# Sheet1.net
KiCad netlist of a schematic drawn in Altium Designer
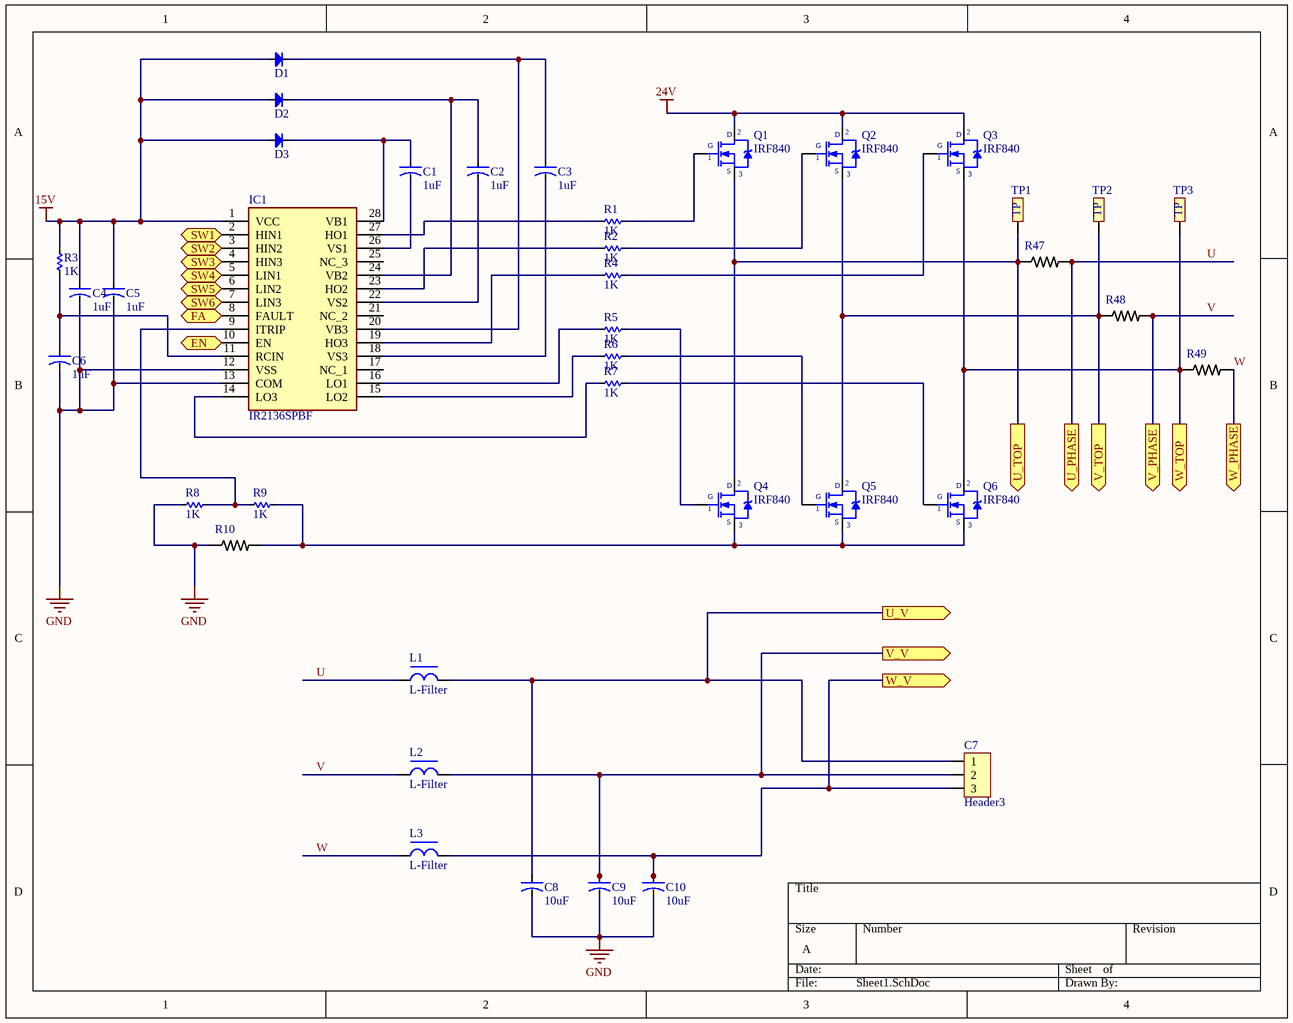
[diagram p0: Sheet1.SchDoc]

(export (version "E")
  (design (tool "Eeschema 10.0.6"))
  (components
    (comp (ref "C1")
      (value "1uF")
      (footprint "CA-ALU-2.54")
      (description "Capacitor (Semiconductor SIM Model)")
      (fields (field (name "PUBLISHER") "Altium Limited"))
      (libsource (lib "LIBRARY") (part "CN-ALU-DIP"))
    )
    (comp (ref "C2")
      (value "1uF")
      (footprint "CA-ALU-2.54")
      (description "Capacitor (Semiconductor SIM Model)")
      (fields (field (name "PUBLISHER") "Altium Limited"))
      (libsource (lib "LIBRARY") (part "CN-ALU-DIP"))
    )
    (comp (ref "C3")
      (value "1uF")
      (footprint "CA-ALU-2.54")
      (description "Capacitor (Semiconductor SIM Model)")
      (fields (field (name "PUBLISHER") "Altium Limited"))
      (libsource (lib "LIBRARY") (part "CN-ALU-DIP"))
    )
    (comp (ref "C4")
      (value "1uF")
      (footprint "CA-ALU-2.54")
      (description "Capacitor (Semiconductor SIM Model)")
      (fields (field (name "PUBLISHER") "Altium Limited"))
      (libsource (lib "LIBRARY") (part "CN-ALU-DIP"))
    )
    (comp (ref "C5")
      (value "1uF")
      (footprint "CA-ALU-2.54")
      (description "Capacitor (Semiconductor SIM Model)")
      (fields (field (name "PUBLISHER") "Altium Limited"))
      (libsource (lib "LIBRARY") (part "CN-ALU-DIP"))
    )
    (comp (ref "C6")
      (value "1uF")
      (footprint "CA-ALU-2.54")
      (description "Capacitor (Semiconductor SIM Model)")
      (fields (field (name "PUBLISHER") "Altium Limited"))
      (libsource (lib "LIBRARY") (part "CN-ALU-DIP"))
    )
    (comp (ref "C7")
      (value "Header3")
      (footprint "HDR3")
      (description "Header IDC, 3 x 1 Pin Vertical 2.54mm Pitch (Non-Boxed, Male)")
      (fields
        (field (name "MANUFACTURER") "Würth Elektronik eiSos GmbH")
        (field (name "PARTNO") "613002143121")
        (field (name "CREATED BY") "Karrer Zheng")
      )
      (libsource (lib "LIBRARY") (part "Header3"))
    )
    (comp (ref "C8")
      (value "10uF")
      (footprint "CA-ALU-2.54")
      (description "Capacitor (Semiconductor SIM Model)")
      (fields (field (name "PUBLISHER") "Altium Limited"))
      (libsource (lib "LIBRARY") (part "CN-ALU-DIP"))
    )
    (comp (ref "C9")
      (value "10uF")
      (footprint "CA-ALU-2.54")
      (description "Capacitor (Semiconductor SIM Model)")
      (fields (field (name "PUBLISHER") "Altium Limited"))
      (libsource (lib "LIBRARY") (part "CN-ALU-DIP"))
    )
    (comp (ref "C10")
      (value "10uF")
      (footprint "CA-ALU-2.54")
      (description "Capacitor (Semiconductor SIM Model)")
      (fields (field (name "PUBLISHER") "Altium Limited"))
      (libsource (lib "LIBRARY") (part "CN-ALU-DIP"))
    )
    (comp (ref "D1")
      (value "Diode")
      (footprint "DIO-1A")
      (description "Default Diode")
      (fields (field (name "PUBLISHER") "Altium Limited"))
      (libsource (lib "LIBRARY") (part "Diode"))
    )
    (comp (ref "D2")
      (value "Diode")
      (footprint "DIO-1A")
      (description "Default Diode")
      (fields (field (name "PUBLISHER") "Altium Limited"))
      (libsource (lib "LIBRARY") (part "Diode"))
    )
    (comp (ref "D3")
      (value "Diode")
      (footprint "DIO-1A")
      (description "Default Diode")
      (fields (field (name "PUBLISHER") "Altium Limited"))
      (libsource (lib "LIBRARY") (part "Diode"))
    )
    (comp (ref "IC1")
      (value "IR2136SPBF")
      (footprint "SOIC127P1032X265-28N")
      (description "Integrated Circuit")
      (fields (field (name "MOUSER PART NUMBER") "942-IR2136SPBF") (field (name "RS PART NUMBER") "5412284P"))
      (libsource (lib "SemacSYS") (part "IR2136SPBF"))
    )
    (comp (ref "L1")
      (value "L-Filter")
      (footprint "L-DIP-M-5.3")
      (description "Inductor")
      (libsource (lib "LIBRARY") (part "L-DIP-1"))
    )
    (comp (ref "L2")
      (value "L-Filter")
      (footprint "L-DIP-M-5.3")
      (description "Inductor")
      (libsource (lib "LIBRARY") (part "L-DIP-1"))
    )
    (comp (ref "L3")
      (value "L-Filter")
      (footprint "L-DIP-M-5.3")
      (description "Inductor")
      (libsource (lib "LIBRARY") (part "L-DIP-1"))
    )
    (comp (ref "Q1")
      (value "IRF840")
      (footprint "TO220H1")
      (description "MOSFET N - CHANNEL 500V - 0.75 - 8A - TO-220")
      (libsource (lib "LIBRARY") (part "IRF840"))
    )
    (comp (ref "Q2")
      (value "IRF840")
      (footprint "TO220H1")
      (description "MOSFET N - CHANNEL 500V - 0.75 - 8A - TO-220")
      (libsource (lib "LIBRARY") (part "IRF840"))
    )
    (comp (ref "Q3")
      (value "IRF840")
      (footprint "TO220H1")
      (description "MOSFET N - CHANNEL 500V - 0.75 - 8A - TO-220")
      (libsource (lib "LIBRARY") (part "IRF840"))
    )
    (comp (ref "Q4")
      (value "IRF840")
      (footprint "TO220H1")
      (description "MOSFET N - CHANNEL 500V - 0.75 - 8A - TO-220")
      (libsource (lib "LIBRARY") (part "IRF840"))
    )
    (comp (ref "Q5")
      (value "IRF840")
      (footprint "TO220H1")
      (description "MOSFET N - CHANNEL 500V - 0.75 - 8A - TO-220")
      (libsource (lib "LIBRARY") (part "IRF840"))
    )
    (comp (ref "Q6")
      (value "IRF840")
      (footprint "TO220H1")
      (description "MOSFET N - CHANNEL 500V - 0.75 - 8A - TO-220")
      (libsource (lib "LIBRARY") (part "IRF840"))
    )
    (comp (ref "R1")
      (value "1K")
      (footprint "RES-1/2W")
      (description "Res")
      (fields
        (field (name "MANUFACTURER") "Generic Components")
        (field (name "PUBLISHER") "Altium Hobart Technology Centre")
      )
      (libsource (lib "LIBRARY1") (part "Res"))
    )
    (comp (ref "R2")
      (value "1K")
      (footprint "RES-1/2W")
      (description "Res")
      (fields
        (field (name "MANUFACTURER") "Generic Components")
        (field (name "PUBLISHER") "Altium Hobart Technology Centre")
      )
      (libsource (lib "LIBRARY1") (part "Res"))
    )
    (comp (ref "R3")
      (value "1K")
      (footprint "RES-1/2W")
      (description "Res")
      (fields
        (field (name "MANUFACTURER") "Generic Components")
        (field (name "PUBLISHER") "Altium Hobart Technology Centre")
      )
      (libsource (lib "LIBRARY1") (part "Res"))
    )
    (comp (ref "R4")
      (value "1K")
      (footprint "RES-1/2W")
      (description "Res")
      (fields
        (field (name "MANUFACTURER") "Generic Components")
        (field (name "PUBLISHER") "Altium Hobart Technology Centre")
      )
      (libsource (lib "LIBRARY1") (part "Res"))
    )
    (comp (ref "R5")
      (value "1K")
      (footprint "RES-1/2W")
      (description "Res")
      (fields
        (field (name "MANUFACTURER") "Generic Components")
        (field (name "PUBLISHER") "Altium Hobart Technology Centre")
      )
      (libsource (lib "LIBRARY1") (part "Res"))
    )
    (comp (ref "R6")
      (value "1K")
      (footprint "RES-1/2W")
      (description "Res")
      (fields
        (field (name "MANUFACTURER") "Generic Components")
        (field (name "PUBLISHER") "Altium Hobart Technology Centre")
      )
      (libsource (lib "LIBRARY1") (part "Res"))
    )
    (comp (ref "R7")
      (value "1K")
      (footprint "RES-1/2W")
      (description "Res")
      (fields
        (field (name "MANUFACTURER") "Generic Components")
        (field (name "PUBLISHER") "Altium Hobart Technology Centre")
      )
      (libsource (lib "LIBRARY1") (part "Res"))
    )
    (comp (ref "R8")
      (value "1K")
      (footprint "RES-1/2W")
      (description "Res")
      (fields
        (field (name "MANUFACTURER") "Generic Components")
        (field (name "PUBLISHER") "Altium Hobart Technology Centre")
      )
      (libsource (lib "LIBRARY1") (part "Res"))
    )
    (comp (ref "R9")
      (value "1K")
      (footprint "RES-1/2W")
      (description "Res")
      (fields
        (field (name "MANUFACTURER") "Generic Components")
        (field (name "PUBLISHER") "Altium Hobart Technology Centre")
      )
      (libsource (lib "LIBRARY1") (part "Res"))
    )
    (comp (ref "R10")
      (value "1-1625873-0")
      (footprint "*RESAD640W45L370D200")
      (description "RS LR0204 RESISTOR KIT")
      (fields (field (name "MF") "TE Connectivity AMP Connectors") (field (name "MP") "RES KIT LR0204R"))
      (libsource (lib "SemacSYS") (part "RES_KIT_LR0204R"))
    )
    (comp (ref "R47")
      (value "1-1625873-0")
      (footprint "*RESAD640W45L370D200")
      (description "RS LR0204 RESISTOR KIT")
      (fields (field (name "MF") "TE Connectivity AMP Connectors") (field (name "MP") "RES KIT LR0204R"))
      (libsource (lib "SemacSYS") (part "RES_KIT_LR0204R"))
    )
    (comp (ref "R48")
      (value "1-1625873-0")
      (footprint "*RESAD640W45L370D200")
      (description "RS LR0204 RESISTOR KIT")
      (fields (field (name "MF") "TE Connectivity AMP Connectors") (field (name "MP") "RES KIT LR0204R"))
      (libsource (lib "SemacSYS") (part "RES_KIT_LR0204R"))
    )
    (comp (ref "R49")
      (value "1-1625873-0")
      (footprint "*RESAD640W45L370D200")
      (description "RS LR0204 RESISTOR KIT")
      (fields (field (name "MF") "TE Connectivity AMP Connectors") (field (name "MP") "RES KIT LR0204R"))
      (libsource (lib "SemacSYS") (part "RES_KIT_LR0204R"))
    )
    (comp (ref "TP1")
      (value "~")
      (footprint "TP")
      (description "CONNECT 1")
      (libsource (lib "syhaunguyen") (part "TP"))
    )
    (comp (ref "TP2")
      (value "~")
      (footprint "TP")
      (description "CONNECT 1")
      (libsource (lib "syhaunguyen") (part "TP"))
    )
    (comp (ref "TP3")
      (value "~")
      (footprint "TP")
      (description "CONNECT 1")
      (libsource (lib "syhaunguyen") (part "TP"))
    )
  )
  (nets
    (net (code "1") (name "/EN") (class "Default")
      (node (ref "IC1") (pin "10") (pinfunction "EN_10") (pintype "passive"))
    )
    (net (code "2") (name "/FA") (class "Default")
      (node (ref "IC1") (pin "8") (pinfunction "FAULT_8") (pintype "passive"))
    )
    (net (code "3") (name "/SW1") (class "Default")
      (node (ref "IC1") (pin "2") (pinfunction "HIN1_2") (pintype "passive"))
    )
    (net (code "4") (name "/SW2") (class "Default")
      (node (ref "IC1") (pin "3") (pinfunction "HIN2_3") (pintype "passive"))
    )
    (net (code "5") (name "/SW3") (class "Default")
      (node (ref "IC1") (pin "4") (pinfunction "HIN3_4") (pintype "passive"))
    )
    (net (code "6") (name "/SW4") (class "Default")
      (node (ref "IC1") (pin "5") (pinfunction "LIN1_5") (pintype "passive"))
    )
    (net (code "7") (name "/SW5") (class "Default")
      (node (ref "IC1") (pin "6") (pinfunction "LIN2_6") (pintype "passive"))
    )
    (net (code "8") (name "/SW6") (class "Default")
      (node (ref "IC1") (pin "7") (pinfunction "LIN3_7") (pintype "passive"))
    )
    (net (code "9") (name "/U") (class "Default")
      (node (ref "L1") (pin "1") (pinfunction "1_1") (pintype "passive"))
      (node (ref "R47") (pin "2") (pinfunction "2_2") (pintype "passive"))
    )
    (net (code "10") (name "/U_TOP") (class "Default")
      (node (ref "Q1") (pin "3") (pinfunction "S_3") (pintype "passive"))
      (node (ref "Q4") (pin "2") (pinfunction "D_2") (pintype "passive"))
      (node (ref "R47") (pin "1") (pinfunction "1_1") (pintype "passive"))
      (node (ref "TP1") (pin "TP1") (pinfunction "0_TP1") (pintype "passive"))
    )
    (net (code "11") (name "/U_V") (class "Default")
      (node (ref "C7") (pin "1") (pinfunction "1_1") (pintype "passive"))
      (node (ref "C8") (pin "1") (pinfunction "1_1") (pintype "passive"))
      (node (ref "L1") (pin "2") (pinfunction "2_2") (pintype "passive"))
    )
    (net (code "12") (name "/V") (class "Default")
      (node (ref "L2") (pin "1") (pinfunction "1_1") (pintype "passive"))
      (node (ref "R48") (pin "2") (pinfunction "2_2") (pintype "passive"))
    )
    (net (code "13") (name "/V_TOP") (class "Default")
      (node (ref "Q2") (pin "3") (pinfunction "S_3") (pintype "passive"))
      (node (ref "Q5") (pin "2") (pinfunction "D_2") (pintype "passive"))
      (node (ref "R48") (pin "1") (pinfunction "1_1") (pintype "passive"))
      (node (ref "TP2") (pin "TP1") (pinfunction "0_TP1") (pintype "passive"))
    )
    (net (code "14") (name "/V_V") (class "Default")
      (node (ref "C7") (pin "2") (pinfunction "2_2") (pintype "passive"))
      (node (ref "C9") (pin "1") (pinfunction "1_1") (pintype "passive"))
      (node (ref "L2") (pin "2") (pinfunction "2_2") (pintype "passive"))
    )
    (net (code "15") (name "/W") (class "Default")
      (node (ref "L3") (pin "1") (pinfunction "1_1") (pintype "passive"))
      (node (ref "R49") (pin "2") (pinfunction "2_2") (pintype "passive"))
    )
    (net (code "16") (name "/W_TOP") (class "Default")
      (node (ref "Q3") (pin "3") (pinfunction "S_3") (pintype "passive"))
      (node (ref "Q6") (pin "2") (pinfunction "D_2") (pintype "passive"))
      (node (ref "R49") (pin "1") (pinfunction "1_1") (pintype "passive"))
      (node (ref "TP3") (pin "TP1") (pinfunction "0_TP1") (pintype "passive"))
    )
    (net (code "17") (name "/W_V") (class "Default")
      (node (ref "C10") (pin "1") (pinfunction "1_1") (pintype "passive"))
      (node (ref "C7") (pin "3") (pinfunction "3_3") (pintype "passive"))
      (node (ref "L3") (pin "2") (pinfunction "2_2") (pintype "passive"))
    )
    (net (code "18") (name "15V") (class "Default")
      (node (ref "C4") (pin "1") (pinfunction "1_1") (pintype "passive"))
      (node (ref "C5") (pin "1") (pinfunction "1_1") (pintype "passive"))
      (node (ref "D1") (pin "1") (pinfunction "A_1") (pintype "passive"))
      (node (ref "D2") (pin "1") (pinfunction "A_1") (pintype "passive"))
      (node (ref "D3") (pin "1") (pinfunction "A_1") (pintype "passive"))
      (node (ref "IC1") (pin "1") (pinfunction "VCC_1") (pintype "passive"))
      (node (ref "R3") (pin "1") (pinfunction "1_1") (pintype "passive"))
    )
    (net (code "19") (name "24V") (class "Default")
      (node (ref "Q1") (pin "2") (pinfunction "D_2") (pintype "passive"))
      (node (ref "Q2") (pin "2") (pinfunction "D_2") (pintype "passive"))
      (node (ref "Q3") (pin "2") (pinfunction "D_2") (pintype "passive"))
    )
    (net (code "20") (name "GND") (class "Default")
      (node (ref "C10") (pin "2") (pinfunction "2_2") (pintype "passive"))
      (node (ref "C4") (pin "2") (pinfunction "2_2") (pintype "passive"))
      (node (ref "C5") (pin "2") (pinfunction "2_2") (pintype "passive"))
      (node (ref "C6") (pin "2") (pinfunction "2_2") (pintype "passive"))
      (node (ref "C8") (pin "2") (pinfunction "2_2") (pintype "passive"))
      (node (ref "C9") (pin "2") (pinfunction "2_2") (pintype "passive"))
      (node (ref "IC1") (pin "12") (pinfunction "VSS_12") (pintype "passive"))
      (node (ref "IC1") (pin "13") (pinfunction "COM_13") (pintype "passive"))
      (node (ref "R10") (pin "1") (pinfunction "1_1") (pintype "passive"))
      (node (ref "R8") (pin "2") (pinfunction "2_2") (pintype "passive"))
    )
    (net (code "21") (name "Net-(D1-K)") (class "Default")
      (node (ref "C3") (pin "1") (pinfunction "1_1") (pintype "passive"))
      (node (ref "D1") (pin "2") (pinfunction "K_2") (pintype "passive"))
      (node (ref "IC1") (pin "20") (pinfunction "VB3_20") (pintype "passive"))
    )
    (net (code "22") (name "Net-(D2-K)") (class "Default")
      (node (ref "C2") (pin "1") (pinfunction "1_1") (pintype "passive"))
      (node (ref "D2") (pin "2") (pinfunction "K_2") (pintype "passive"))
      (node (ref "IC1") (pin "24") (pinfunction "VB2_24") (pintype "passive"))
    )
    (net (code "23") (name "Net-(D3-K)") (class "Default")
      (node (ref "C1") (pin "1") (pinfunction "1_1") (pintype "passive"))
      (node (ref "D3") (pin "2") (pinfunction "K_2") (pintype "passive"))
      (node (ref "IC1") (pin "28") (pinfunction "VB1_28") (pintype "passive"))
    )
    (net (code "24") (name "Net-(IC1-HO1)") (class "Default")
      (node (ref "IC1") (pin "27") (pinfunction "HO1_27") (pintype "passive"))
      (node (ref "R1") (pin "2") (pinfunction "2_2") (pintype "passive"))
    )
    (net (code "25") (name "Net-(IC1-HO2)") (class "Default")
      (node (ref "IC1") (pin "23") (pinfunction "HO2_23") (pintype "passive"))
      (node (ref "R2") (pin "2") (pinfunction "2_2") (pintype "passive"))
    )
    (net (code "26") (name "Net-(IC1-HO3)") (class "Default")
      (node (ref "IC1") (pin "19") (pinfunction "HO3_19") (pintype "passive"))
      (node (ref "R4") (pin "2") (pinfunction "2_2") (pintype "passive"))
    )
    (net (code "27") (name "Net-(IC1-ITRIP)") (class "Default")
      (node (ref "IC1") (pin "9") (pinfunction "ITRIP_9") (pintype "passive"))
      (node (ref "R8") (pin "1") (pinfunction "1_1") (pintype "passive"))
      (node (ref "R9") (pin "2") (pinfunction "2_2") (pintype "passive"))
    )
    (net (code "28") (name "Net-(IC1-LO1)") (class "Default")
      (node (ref "IC1") (pin "16") (pinfunction "LO1_16") (pintype "passive"))
      (node (ref "R5") (pin "2") (pinfunction "2_2") (pintype "passive"))
    )
    (net (code "29") (name "Net-(IC1-LO2)") (class "Default")
      (node (ref "IC1") (pin "15") (pinfunction "LO2_15") (pintype "passive"))
      (node (ref "R6") (pin "2") (pinfunction "2_2") (pintype "passive"))
    )
    (net (code "30") (name "Net-(IC1-LO3)") (class "Default")
      (node (ref "IC1") (pin "14") (pinfunction "LO3_14") (pintype "passive"))
      (node (ref "R7") (pin "2") (pinfunction "2_2") (pintype "passive"))
    )
    (net (code "31") (name "Net-(IC1-RCIN)") (class "Default")
      (node (ref "C6") (pin "1") (pinfunction "1_1") (pintype "passive"))
      (node (ref "IC1") (pin "11") (pinfunction "RCIN_11") (pintype "passive"))
      (node (ref "R3") (pin "2") (pinfunction "2_2") (pintype "passive"))
    )
    (net (code "32") (name "Net-(IC1-VS1)") (class "Default")
      (node (ref "C1") (pin "2") (pinfunction "2_2") (pintype "passive"))
      (node (ref "IC1") (pin "26") (pinfunction "VS1_26") (pintype "passive"))
    )
    (net (code "33") (name "Net-(IC1-VS2)") (class "Default")
      (node (ref "C2") (pin "2") (pinfunction "2_2") (pintype "passive"))
      (node (ref "IC1") (pin "22") (pinfunction "VS2_22") (pintype "passive"))
    )
    (net (code "34") (name "Net-(IC1-VS3)") (class "Default")
      (node (ref "C3") (pin "2") (pinfunction "2_2") (pintype "passive"))
      (node (ref "IC1") (pin "18") (pinfunction "VS3_18") (pintype "passive"))
    )
    (net (code "35") (name "Net-(Q1-G)") (class "Default")
      (node (ref "Q1") (pin "1") (pinfunction "G_1") (pintype "passive"))
      (node (ref "R1") (pin "1") (pinfunction "1_1") (pintype "passive"))
    )
    (net (code "36") (name "Net-(Q2-G)") (class "Default")
      (node (ref "Q2") (pin "1") (pinfunction "G_1") (pintype "passive"))
      (node (ref "R2") (pin "1") (pinfunction "1_1") (pintype "passive"))
    )
    (net (code "37") (name "Net-(Q3-G)") (class "Default")
      (node (ref "Q3") (pin "1") (pinfunction "G_1") (pintype "passive"))
      (node (ref "R4") (pin "1") (pinfunction "1_1") (pintype "passive"))
    )
    (net (code "38") (name "Net-(Q4-G)") (class "Default")
      (node (ref "Q4") (pin "1") (pinfunction "G_1") (pintype "passive"))
      (node (ref "R5") (pin "1") (pinfunction "1_1") (pintype "passive"))
    )
    (net (code "39") (name "Net-(Q4-S)") (class "Default")
      (node (ref "Q4") (pin "3") (pinfunction "S_3") (pintype "passive"))
      (node (ref "Q5") (pin "3") (pinfunction "S_3") (pintype "passive"))
      (node (ref "Q6") (pin "3") (pinfunction "S_3") (pintype "passive"))
      (node (ref "R10") (pin "2") (pinfunction "2_2") (pintype "passive"))
      (node (ref "R9") (pin "1") (pinfunction "1_1") (pintype "passive"))
    )
    (net (code "40") (name "Net-(Q5-G)") (class "Default")
      (node (ref "Q5") (pin "1") (pinfunction "G_1") (pintype "passive"))
      (node (ref "R6") (pin "1") (pinfunction "1_1") (pintype "passive"))
    )
    (net (code "41") (name "Net-(Q6-G)") (class "Default")
      (node (ref "Q6") (pin "1") (pinfunction "G_1") (pintype "passive"))
      (node (ref "R7") (pin "1") (pinfunction "1_1") (pintype "passive"))
    )
    (net (code "42") (name "unconnected-(IC1-NC_1-Pad17)") (class "Default")
      (node (ref "IC1") (pin "17") (pinfunction "NC_1_17") (pintype "passive"))
    )
    (net (code "43") (name "unconnected-(IC1-NC_2-Pad21)") (class "Default")
      (node (ref "IC1") (pin "21") (pinfunction "NC_2_21") (pintype "passive"))
    )
    (net (code "44") (name "unconnected-(IC1-NC_3-Pad25)") (class "Default")
      (node (ref "IC1") (pin "25") (pinfunction "NC_3_25") (pintype "passive"))
    )
  )
)
